# MotorDriver.net
KiCad netlist of a schematic drawn in Altium Designer
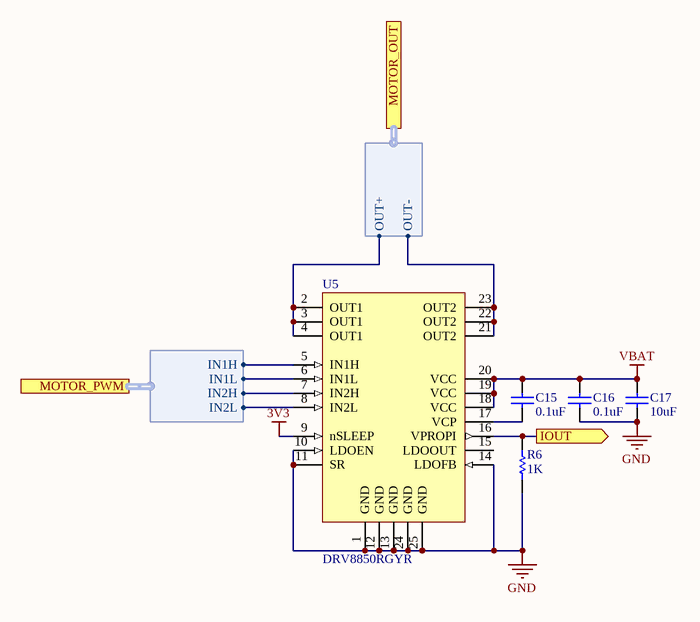
[diagram p0: MotorDriver.SchDoc]

(export (version "E")
  (design (tool "Eeschema 10.0.6"))
  (components
    (comp (ref "C15")
      (value "0.1uF")
      (footprint "C0402[1005X55]")
      (description "0.1uF 100V 10% 0402 (1005 Metric)")
      (fields (field (name "PARTNUMBER") "GRM155R62A104KE14D") (field (name "MANUFACTURER") "Murata"))
      (libsource (lib "Capacitors") (part "CAP_0.1uF_100V_0402_10%"))
    )
    (comp (ref "C16")
      (value "0.1uF")
      (footprint "C0402[1005X55]")
      (description "0.1uF 6.3V 10% 0402 (1005 Metric)")
      (fields (field (name "PARTNUMBER") "GRM155R70J104KA01D") (field (name "MANUFACTURER") "Murata"))
      (libsource (lib "Capacitors") (part "CAP_0.1uF_6.3V_0402_10%"))
    )
    (comp (ref "C17")
      (value "10uF")
      (footprint "C0402[1005X55]")
      (description "10uF 6.3V 20% 0402 (1005 Metric)")
      (fields (field (name "PARTNUMBER") "GRM155R60J106ME44D") (field (name "MANUFACTURER") "Murata"))
      (libsource (lib "Capacitors") (part "CAP_10uF_6.3V_0402_20%"))
    )
    (comp (ref "R6")
      (value "1K")
      (footprint "R0402[1005]")
      (description "1K 0.063W 1% 0402 (1005 Metric)")
      (fields (field (name "MANUFACTURER") "KOA Speer") (field (name "PARTNUMBER") "RK73H1ETTP1001F"))
      (libsource (lib "Resistors") (part "RES_1K_0402_1%"))
    )
    (comp (ref "U5")
      (value "DRV8850RGYR")
      (footprint "VQFN-24 (5.5X3.5MM)")
      (description "IC MOTOR DRIVER PAR 24VQFN")
      (fields (field (name "MANUFACTURER") "Texas Instruments"))
      (libsource (lib "ICs") (part "DRV8850RGYR"))
    )
  )
  (nets
    (net (code "3") (name "/IN1H") (class "Default")
      (node (ref "U5") (pin "5") (pinfunction "IN1H_5") (pintype "input"))
    )
    (net (code "4") (name "/IN1L") (class "Default")
      (node (ref "U5") (pin "6") (pinfunction "IN1L_6") (pintype "input"))
    )
    (net (code "5") (name "/IN2H") (class "Default")
      (node (ref "U5") (pin "7") (pinfunction "IN2H_7") (pintype "input"))
    )
    (net (code "6") (name "/IN2L") (class "Default")
      (node (ref "U5") (pin "8") (pinfunction "IN2L_8") (pintype "input"))
    )
    (net (code "7") (name "/IOUT") (class "Default")
      (node (ref "R6") (pin "2") (pinfunction "2_2") (pintype "passive"))
      (node (ref "U5") (pin "16") (pinfunction "VPROPI_16") (pintype "output"))
    )
    (net (code "8") (name "/OUT+") (class "Default")
      (node (ref "U5") (pin "2") (pinfunction "OUT1_2") (pintype "power_in"))
      (node (ref "U5") (pin "3") (pinfunction "OUT1_3") (pintype "power_in"))
      (node (ref "U5") (pin "4") (pinfunction "OUT1_4") (pintype "power_in"))
    )
    (net (code "9") (name "/OUT-") (class "Default")
      (node (ref "U5") (pin "21") (pinfunction "OUT2_21") (pintype "power_in"))
      (node (ref "U5") (pin "22") (pinfunction "OUT2_22") (pintype "power_in"))
      (node (ref "U5") (pin "23") (pinfunction "OUT2_23") (pintype "power_in"))
    )
    (net (code "12") (name "3V3") (class "Default")
      (node (ref "U5") (pin "9") (pinfunction "nSLEEP_9") (pintype "input"))
    )
    (net (code "13") (name "GND") (class "Default")
      (node (ref "C16") (pin "1") (pinfunction "1_1") (pintype "passive"))
      (node (ref "C17") (pin "1") (pinfunction "1_1") (pintype "passive"))
      (node (ref "R6") (pin "1") (pinfunction "1_1") (pintype "passive"))
      (node (ref "U5") (pin "1") (pinfunction "GND_1") (pintype "power_in"))
      (node (ref "U5") (pin "10") (pinfunction "LDOEN_10") (pintype "input"))
      (node (ref "U5") (pin "11") (pinfunction "SR_11") (pintype "passive"))
      (node (ref "U5") (pin "12") (pinfunction "GND_12") (pintype "power_in"))
      (node (ref "U5") (pin "13") (pinfunction "GND_13") (pintype "power_in"))
      (node (ref "U5") (pin "14") (pinfunction "LDOFB_14") (pintype "input"))
      (node (ref "U5") (pin "24") (pinfunction "GND_24") (pintype "power_in"))
      (node (ref "U5") (pin "25") (pinfunction "GND_25") (pintype "power_in"))
    )
    (net (code "14") (name "Net-(U5-VCP)") (class "Default")
      (node (ref "C15") (pin "2") (pinfunction "2_2") (pintype "passive"))
      (node (ref "U5") (pin "17") (pinfunction "VCP_17") (pintype "power_in"))
    )
    (net (code "15") (name "VBAT") (class "Default")
      (node (ref "C15") (pin "1") (pinfunction "1_1") (pintype "passive"))
      (node (ref "C16") (pin "2") (pinfunction "2_2") (pintype "passive"))
      (node (ref "C17") (pin "2") (pinfunction "2_2") (pintype "passive"))
      (node (ref "U5") (pin "18") (pinfunction "VCC_18") (pintype "power_in"))
      (node (ref "U5") (pin "19") (pinfunction "VCC_19") (pintype "power_in"))
      (node (ref "U5") (pin "20") (pinfunction "VCC_20") (pintype "power_in"))
    )
    (net (code "16") (name "unconnected-(U5-LDOOUT-Pad15)") (class "Default")
      (node (ref "U5") (pin "15") (pinfunction "LDOOUT_15") (pintype "power_in"))
    )
  )
)
